# RAK3172-Breakout.net
KiCad netlist of a schematic drawn in EAGLE
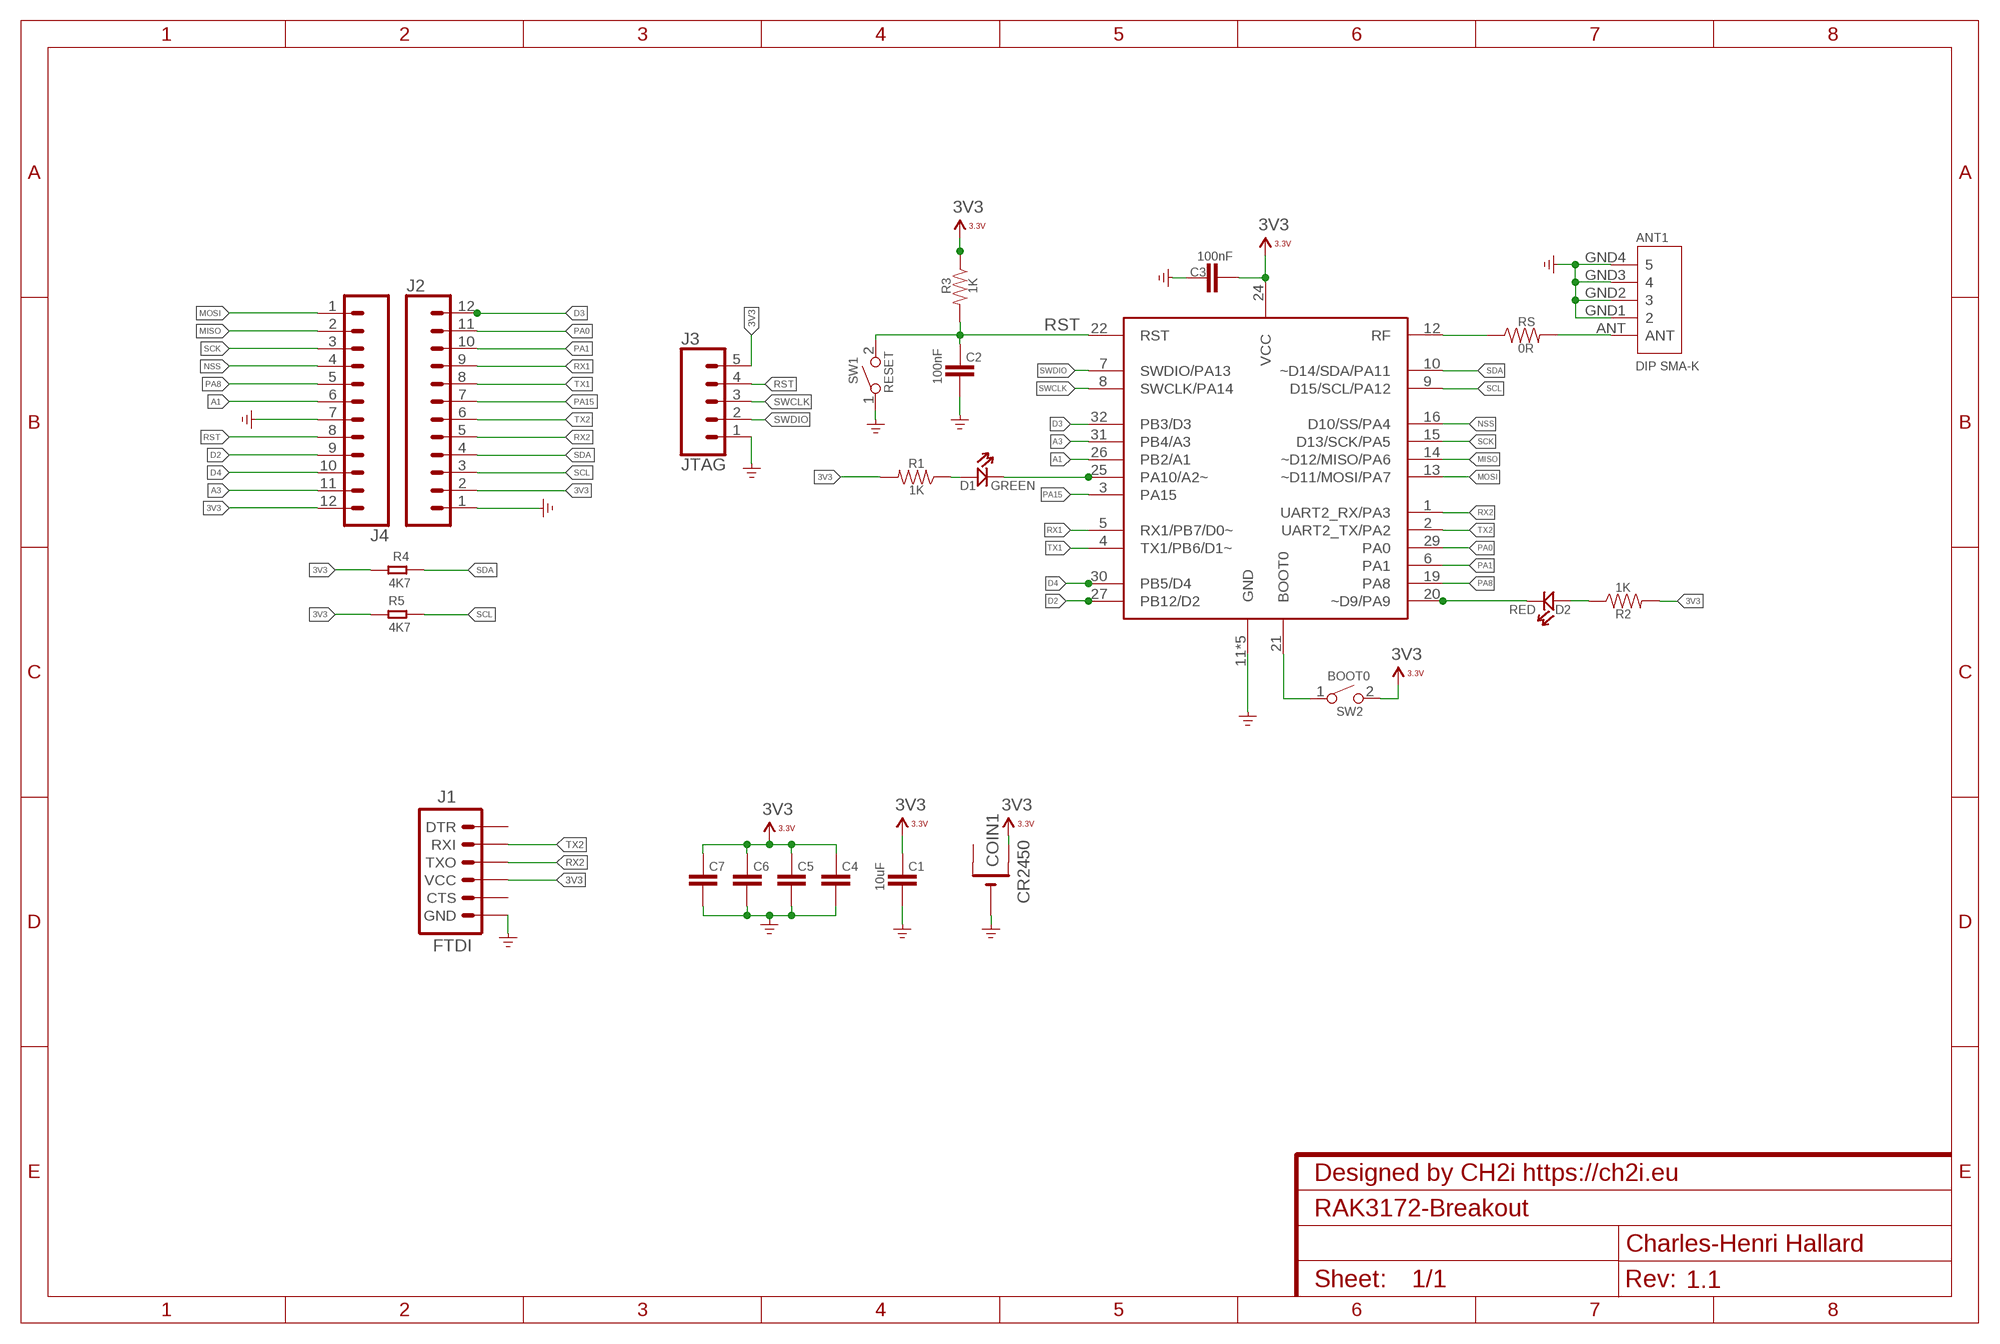
[diagram p0: schematic, sheet 1]

(export (version "E")
  (design (tool "Eeschema 10.0.6"))
  (components
    (comp (ref "ANT1")
      (value "DIP SMA-K")
      (footprint "eagle-import:SMA5P-SMD-5.1-6.5X6.5X16.5MM")
      (libsource (lib "eagle-import") (part "ANTENNA-SMA-MCX-JE-320160125"))
    )
    (comp (ref "C1")
      (value "10uF")
      (footprint "eagle-import:0805-CAP")
      (libsource (lib "eagle-import") (part "CAP0805-CAP"))
    )
    (comp (ref "C2")
      (value "100nF")
      (footprint "eagle-import:0805-CAP")
      (libsource (lib "eagle-import") (part "CAP0805-CAP"))
    )
    (comp (ref "C3")
      (value "100nF")
      (footprint "eagle-import:0805-CAP")
      (libsource (lib "eagle-import") (part "CAP0805-CAP"))
    )
    (comp (ref "C4")
      (value "100uF")
      (footprint "eagle-import:0805-CAP")
      (libsource (lib "eagle-import") (part "CAP0805-CAP"))
    )
    (comp (ref "C5")
      (value "100uF")
      (footprint "eagle-import:0805-CAP")
      (libsource (lib "eagle-import") (part "CAP0805-CAP"))
    )
    (comp (ref "C6")
      (value "100uF")
      (footprint "eagle-import:0805-CAP")
      (libsource (lib "eagle-import") (part "CAP0805-CAP"))
    )
    (comp (ref "C7")
      (value "100uF")
      (footprint "eagle-import:0805-CAP")
      (libsource (lib "eagle-import") (part "CAP0805-CAP"))
    )
    (comp (ref "COIN1")
      (value "CR2450")
      (footprint "eagle-import:CR2450-SMD")
      (libsource (lib "eagle-import") (part "CR2450SMD"))
    )
    (comp (ref "D1")
      (value "GREEN")
      (footprint "eagle-import:LED-0805")
      (libsource (lib "eagle-import") (part "LED'0805'"))
    )
    (comp (ref "D2")
      (value "RED")
      (footprint "eagle-import:LED-0805")
      (libsource (lib "eagle-import") (part "LED'0805'"))
    )
    (comp (ref "J1")
      (value "FTDI")
      (footprint "eagle-import:1X06-SMD_RA_MALE")
      (libsource (lib "eagle-import") (part "6_PIN_SERIAL_TARGETSMD"))
    )
    (comp (ref "J2")
      (value "CONN_12NO_SILK")
      (footprint "eagle-import:1X12_NO_SILK")
      (libsource (lib "eagle-import") (part "CONN_12NO_SILK"))
    )
    (comp (ref "J3")
      (value "JTAG")
      (footprint "eagle-import:1X05_LOCK")
      (libsource (lib "eagle-import") (part "CONN_05LOCK"))
    )
    (comp (ref "J4")
      (value "CONN_12NO_SILK")
      (footprint "eagle-import:1X12_NO_SILK")
      (libsource (lib "eagle-import") (part "CONN_12NO_SILK"))
    )
    (comp (ref "R1")
      (value "1K")
      (footprint "eagle-import:0805-RES")
      (libsource (lib "eagle-import") (part "RESISTOR0805-RES"))
    )
    (comp (ref "R2")
      (value "1K")
      (footprint "eagle-import:0805-RES")
      (libsource (lib "eagle-import") (part "RESISTOR0805-RES"))
    )
    (comp (ref "R3")
      (value "1K")
      (footprint "eagle-import:0805-RES")
      (libsource (lib "eagle-import") (part "RESISTOR0805-RES"))
    )
    (comp (ref "R4")
      (value "4K7")
      (footprint "eagle-import:R0805")
      (libsource (lib "eagle-import") (part "RES-0805"))
    )
    (comp (ref "R5")
      (value "4K7")
      (footprint "eagle-import:R0805")
      (libsource (lib "eagle-import") (part "RES-0805"))
    )
    (comp (ref "RS")
      (value "0R")
      (footprint "eagle-import:0603-MATCHNET")
      (libsource (lib "eagle-import") (part "RESISTORMATCHINGNETWORK"))
    )
    (comp (ref "SW1")
      (value "RESET")
      (footprint "eagle-import:SW2-2.6-3.0X2.5X1.2+0.4MM")
      (fields (field (name "MPN") "B3U-1000P-2P-SMD"))
      (libsource (lib "eagle-import") (part "SMD-BUTTON(2P-3.0X2.5X1.2+0.4MM)-B3U-1000P-2P-SMD"))
    )
    (comp (ref "SW2")
      (value "BOOT0")
      (footprint "eagle-import:SW2-2.6-3.0X2.5X1.2+0.4MM")
      (fields (field (name "MPN") "B3U-1000P-2P-SMD"))
      (libsource (lib "eagle-import") (part "SMD-BUTTON(2P-3.0X2.5X1.2+0.4MM)-B3U-1000P-2P-SMD"))
    )
    (comp (ref "U$3")
      (value "RAK3172HF")
      (footprint "eagle-import:RAK3172")
      (libsource (lib "eagle-import") (part "RAK3172HF"))
    )
  )
  (nets
    (net (code "1") (name "3V3") (class "Default")
      (node (ref "C1") (pin "2") (pinfunction "2_2") (pintype "passive"))
      (node (ref "C3") (pin "2") (pinfunction "2_2") (pintype "passive"))
      (node (ref "C4") (pin "2") (pinfunction "2_2") (pintype "passive"))
      (node (ref "C5") (pin "2") (pinfunction "2_2") (pintype "passive"))
      (node (ref "C6") (pin "2") (pinfunction "2_2") (pintype "passive"))
      (node (ref "C7") (pin "2") (pinfunction "2_2") (pintype "passive"))
      (node (ref "COIN1") (pin "+$2") (pinfunction "+1_+$2") (pintype "passive"))
      (node (ref "J1") (pin "4") (pinfunction "VCC_4") (pintype "passive"))
      (node (ref "J2") (pin "2") (pinfunction "2_2") (pintype "passive"))
      (node (ref "J3") (pin "5") (pinfunction "5_5") (pintype "passive"))
      (node (ref "J4") (pin "12") (pinfunction "12_12") (pintype "passive"))
      (node (ref "R1") (pin "2") (pinfunction "2_2") (pintype "passive"))
      (node (ref "R2") (pin "2") (pinfunction "2_2") (pintype "passive"))
      (node (ref "R3") (pin "1") (pinfunction "1_1") (pintype "passive"))
      (node (ref "R4") (pin "1") (pinfunction "1_1") (pintype "passive"))
      (node (ref "R5") (pin "1") (pinfunction "1_1") (pintype "passive"))
      (node (ref "SW2") (pin "2") (pinfunction "2_2") (pintype "bidirectional"))
      (node (ref "U$3") (pin "24") (pinfunction "VCC_24") (pintype "power_in"))
    )
    (net (code "2") (name "A1") (class "Default")
      (node (ref "J4") (pin "6") (pinfunction "6_6") (pintype "passive"))
      (node (ref "U$3") (pin "26") (pinfunction "PB2/A1_26") (pintype "bidirectional"))
    )
    (net (code "3") (name "A3") (class "Default")
      (node (ref "J4") (pin "11") (pinfunction "11_11") (pintype "passive"))
      (node (ref "U$3") (pin "31") (pinfunction "PB4/A3_31") (pintype "bidirectional"))
    )
    (net (code "4") (name "D2") (class "Default")
      (node (ref "J4") (pin "9") (pinfunction "9_9") (pintype "passive"))
      (node (ref "U$3") (pin "27") (pinfunction "PB12/D2_27") (pintype "bidirectional"))
    )
    (net (code "5") (name "D3") (class "Default")
      (node (ref "J2") (pin "12") (pinfunction "12_12") (pintype "passive"))
      (node (ref "U$3") (pin "32") (pinfunction "PB3/D3_32") (pintype "bidirectional"))
    )
    (net (code "6") (name "D4") (class "Default")
      (node (ref "J4") (pin "10") (pinfunction "10_10") (pintype "passive"))
      (node (ref "U$3") (pin "30") (pinfunction "PB5/D4_30") (pintype "bidirectional"))
    )
    (net (code "7") (name "GND_POWER") (class "Default")
      (node (ref "ANT1") (pin "GND1") (pinfunction "2_GND1") (pintype "bidirectional"))
      (node (ref "ANT1") (pin "GND2") (pinfunction "3_GND2") (pintype "bidirectional"))
      (node (ref "ANT1") (pin "GND3") (pinfunction "4_GND3") (pintype "bidirectional"))
      (node (ref "ANT1") (pin "GND4") (pinfunction "5_GND4") (pintype "bidirectional"))
      (node (ref "C1") (pin "1") (pinfunction "1_1") (pintype "passive"))
      (node (ref "C2") (pin "1") (pinfunction "1_1") (pintype "passive"))
      (node (ref "C3") (pin "1") (pinfunction "1_1") (pintype "passive"))
      (node (ref "C4") (pin "1") (pinfunction "1_1") (pintype "passive"))
      (node (ref "C5") (pin "1") (pinfunction "1_1") (pintype "passive"))
      (node (ref "C6") (pin "1") (pinfunction "1_1") (pintype "passive"))
      (node (ref "C7") (pin "1") (pinfunction "1_1") (pintype "passive"))
      (node (ref "COIN1") (pin "-") (pinfunction "-_-") (pintype "passive"))
      (node (ref "J1") (pin "6") (pinfunction "GND_6") (pintype "passive"))
      (node (ref "J2") (pin "1") (pinfunction "1_1") (pintype "passive"))
      (node (ref "J3") (pin "1") (pinfunction "1_1") (pintype "passive"))
      (node (ref "J4") (pin "7") (pinfunction "7_7") (pintype "passive"))
      (node (ref "SW1") (pin "1") (pinfunction "1_1") (pintype "bidirectional"))
      (node (ref "U$3") (pin "11") (pinfunction "GND_11") (pintype "power_in"))
      (node (ref "U$3") (pin "17") (pinfunction "GND_17") (pintype "power_in"))
      (node (ref "U$3") (pin "18") (pinfunction "GND_18") (pintype "power_in"))
      (node (ref "U$3") (pin "23") (pinfunction "GND_23") (pintype "power_in"))
      (node (ref "U$3") (pin "28") (pinfunction "GND_28") (pintype "power_in"))
    )
    (net (code "8") (name "MISO") (class "Default")
      (node (ref "J4") (pin "2") (pinfunction "2_2") (pintype "passive"))
      (node (ref "U$3") (pin "14") (pinfunction "~{D12/MISO/PA6}_14") (pintype "bidirectional"))
    )
    (net (code "9") (name "MOSI") (class "Default")
      (node (ref "J4") (pin "1") (pinfunction "1_1") (pintype "passive"))
      (node (ref "U$3") (pin "13") (pinfunction "~{D11/MOSI/PA7}_13") (pintype "bidirectional"))
    )
    (net (code "10") (name "NSS") (class "Default")
      (node (ref "J4") (pin "4") (pinfunction "4_4") (pintype "passive"))
      (node (ref "U$3") (pin "16") (pinfunction "D10/SS/PA4_16") (pintype "bidirectional"))
    )
    (net (code "11") (name "Net-(ANT1-PadANT)") (class "Default")
      (node (ref "ANT1") (pin "ANT") (pinfunction "ANT_ANT") (pintype "bidirectional"))
      (node (ref "RS") (pin "2") (pinfunction "2_2") (pintype "passive"))
    )
    (net (code "12") (name "Net-(D1-Pad+)") (class "Default")
      (node (ref "D1") (pin "+") (pinfunction "+_+") (pintype "passive"))
      (node (ref "R1") (pin "1") (pinfunction "1_1") (pintype "passive"))
    )
    (net (code "13") (name "Net-(D2-Pad+)") (class "Default")
      (node (ref "D2") (pin "+") (pinfunction "+_+") (pintype "passive"))
      (node (ref "R2") (pin "1") (pinfunction "1_1") (pintype "passive"))
    )
    (net (code "14") (name "Net-(U$3-BOOT0)") (class "Default")
      (node (ref "SW2") (pin "1") (pinfunction "1_1") (pintype "bidirectional"))
      (node (ref "U$3") (pin "21") (pinfunction "BOOT0_21") (pintype "input"))
    )
    (net (code "15") (name "Net-(U$3-PA10{slash}A2~{})") (class "Default")
      (node (ref "D1") (pin "-") (pinfunction "-_-") (pintype "passive"))
      (node (ref "U$3") (pin "25") (pinfunction "PA10/A2~{}_25") (pintype "bidirectional"))
    )
    (net (code "16") (name "Net-(U$3-RF)") (class "Default")
      (node (ref "RS") (pin "1") (pinfunction "1_1") (pintype "passive"))
      (node (ref "U$3") (pin "12") (pinfunction "RF_12") (pintype "output"))
    )
    (net (code "17") (name "Net-(U$3-~{D9{slash}PA9})") (class "Default")
      (node (ref "D2") (pin "-") (pinfunction "-_-") (pintype "passive"))
      (node (ref "U$3") (pin "20") (pinfunction "~{D9/PA9}_20") (pintype "bidirectional"))
    )
    (net (code "18") (name "PA0") (class "Default")
      (node (ref "J2") (pin "11") (pinfunction "11_11") (pintype "passive"))
      (node (ref "U$3") (pin "29") (pinfunction "PA0_29") (pintype "bidirectional"))
    )
    (net (code "19") (name "PA1") (class "Default")
      (node (ref "J2") (pin "10") (pinfunction "10_10") (pintype "passive"))
      (node (ref "U$3") (pin "6") (pinfunction "PA1_6") (pintype "bidirectional"))
    )
    (net (code "20") (name "PA8") (class "Default")
      (node (ref "J4") (pin "5") (pinfunction "5_5") (pintype "passive"))
      (node (ref "U$3") (pin "19") (pinfunction "PA8_19") (pintype "bidirectional"))
    )
    (net (code "21") (name "PA15") (class "Default")
      (node (ref "J2") (pin "7") (pinfunction "7_7") (pintype "passive"))
      (node (ref "U$3") (pin "3") (pinfunction "PA15_3") (pintype "bidirectional"))
    )
    (net (code "22") (name "RST") (class "Default")
      (node (ref "C2") (pin "2") (pinfunction "2_2") (pintype "passive"))
      (node (ref "J3") (pin "4") (pinfunction "4_4") (pintype "passive"))
      (node (ref "J4") (pin "8") (pinfunction "8_8") (pintype "passive"))
      (node (ref "R3") (pin "2") (pinfunction "2_2") (pintype "passive"))
      (node (ref "SW1") (pin "2") (pinfunction "2_2") (pintype "bidirectional"))
      (node (ref "U$3") (pin "22") (pinfunction "RST_22") (pintype "input"))
    )
    (net (code "23") (name "RX1") (class "Default")
      (node (ref "J2") (pin "9") (pinfunction "9_9") (pintype "passive"))
      (node (ref "U$3") (pin "5") (pinfunction "RX1/PB7/D0~{}_5") (pintype "bidirectional"))
    )
    (net (code "24") (name "RX2") (class "Default")
      (node (ref "J1") (pin "3") (pinfunction "TXO_3") (pintype "passive"))
      (node (ref "J2") (pin "5") (pinfunction "5_5") (pintype "passive"))
      (node (ref "U$3") (pin "1") (pinfunction "UART2_RX/PA3_1") (pintype "bidirectional"))
    )
    (net (code "25") (name "SCK") (class "Default")
      (node (ref "J4") (pin "3") (pinfunction "3_3") (pintype "passive"))
      (node (ref "U$3") (pin "15") (pinfunction "D13/SCK/PA5_15") (pintype "bidirectional"))
    )
    (net (code "26") (name "SCL") (class "Default")
      (node (ref "J2") (pin "3") (pinfunction "3_3") (pintype "passive"))
      (node (ref "R5") (pin "2") (pinfunction "2_2") (pintype "passive"))
      (node (ref "U$3") (pin "9") (pinfunction "D15/SCL/PA12_9") (pintype "bidirectional"))
    )
    (net (code "27") (name "SDA") (class "Default")
      (node (ref "J2") (pin "4") (pinfunction "4_4") (pintype "passive"))
      (node (ref "R4") (pin "2") (pinfunction "2_2") (pintype "passive"))
      (node (ref "U$3") (pin "10") (pinfunction "~{D14/SDA/PA11}_10") (pintype "bidirectional"))
    )
    (net (code "28") (name "SWCLK") (class "Default")
      (node (ref "J3") (pin "3") (pinfunction "3_3") (pintype "passive"))
      (node (ref "U$3") (pin "8") (pinfunction "SWCLK/PA14_8") (pintype "bidirectional"))
    )
    (net (code "29") (name "SWDIO") (class "Default")
      (node (ref "J3") (pin "2") (pinfunction "2_2") (pintype "passive"))
      (node (ref "U$3") (pin "7") (pinfunction "SWDIO/PA13_7") (pintype "bidirectional"))
    )
    (net (code "30") (name "TX1") (class "Default")
      (node (ref "J2") (pin "8") (pinfunction "8_8") (pintype "passive"))
      (node (ref "U$3") (pin "4") (pinfunction "TX1/PB6/D1~{}_4") (pintype "bidirectional"))
    )
    (net (code "31") (name "TX2") (class "Default")
      (node (ref "J1") (pin "2") (pinfunction "RXI_2") (pintype "passive"))
      (node (ref "J2") (pin "6") (pinfunction "6_6") (pintype "passive"))
      (node (ref "U$3") (pin "2") (pinfunction "UART2_TX/PA2_2") (pintype "bidirectional"))
    )
    (net (code "32") (name "unconnected-(COIN1-+-Pad+$1)") (class "Default")
      (node (ref "COIN1") (pin "+$1") (pinfunction "+_+$1") (pintype "passive"))
    )
    (net (code "33") (name "unconnected-(J1-CTS-Pad5)") (class "Default")
      (node (ref "J1") (pin "5") (pinfunction "CTS_5") (pintype "passive"))
    )
    (net (code "34") (name "unconnected-(J1-DTR-Pad1)") (class "Default")
      (node (ref "J1") (pin "1") (pinfunction "DTR_1") (pintype "passive"))
    )
  )
)
